# d232_board.net
KiCad netlist of a schematic drawn in EAGLE
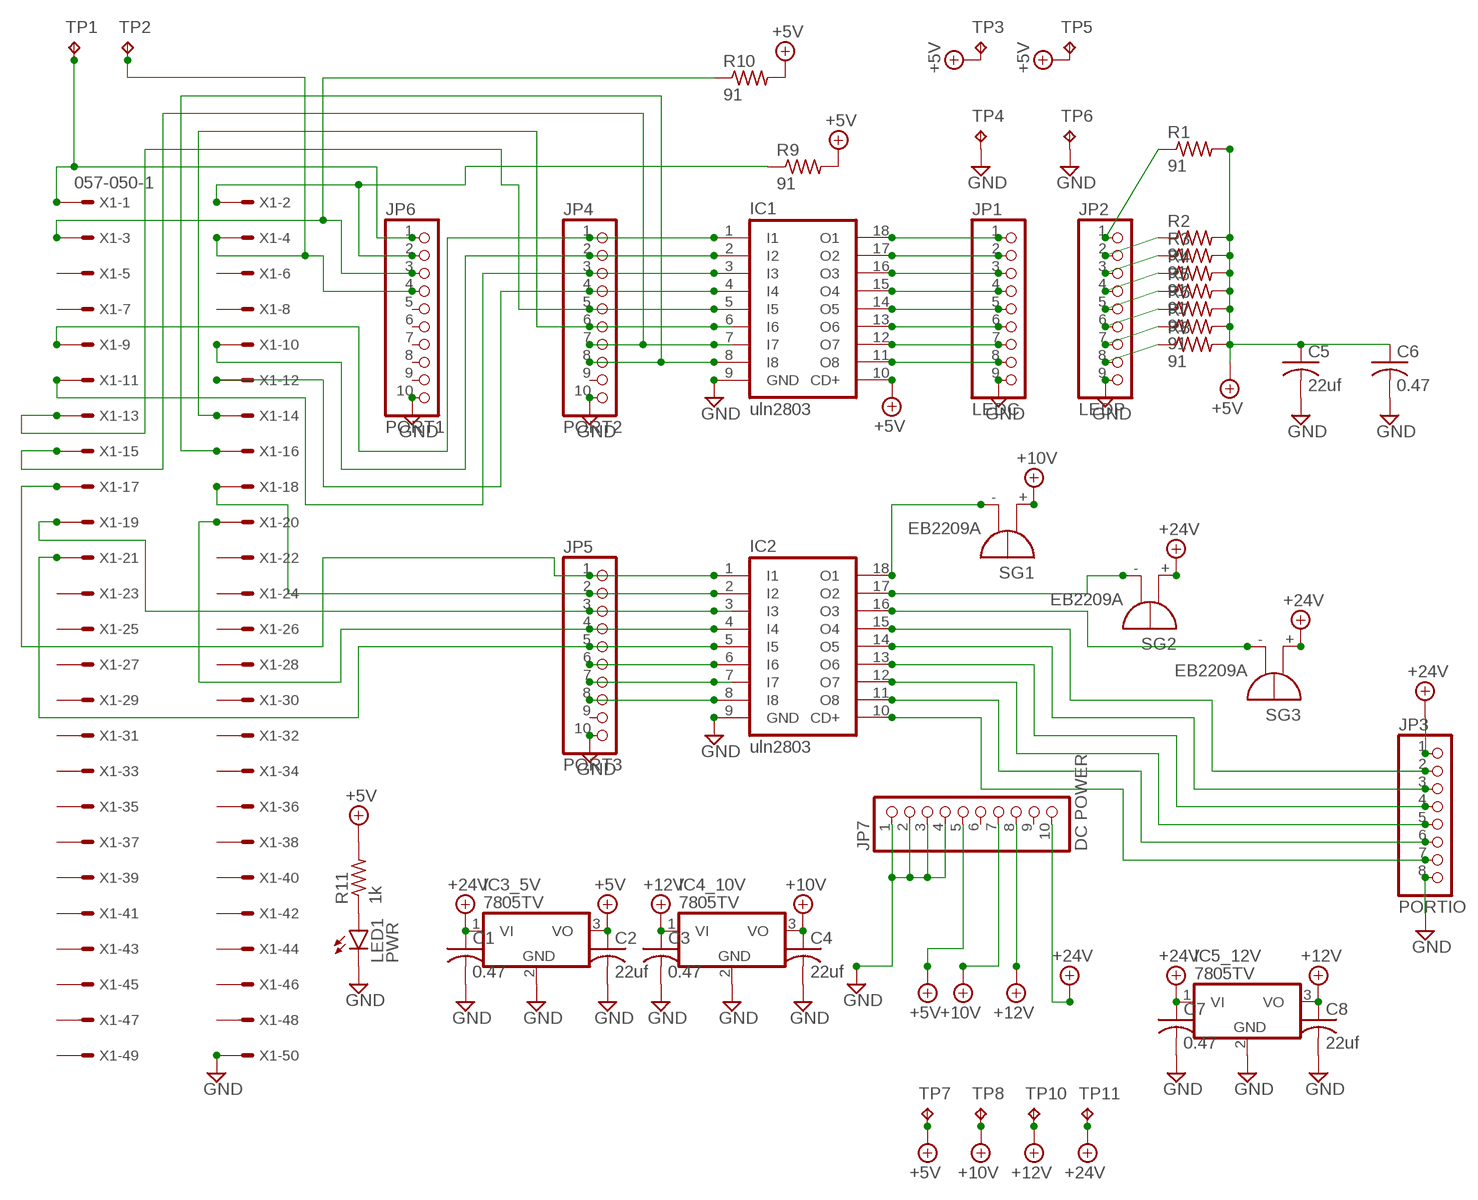
[diagram p0: schematic, sheet 1]

(export (version "E")
  (design (tool "Eeschema 10.0.6"))
  (components
    (comp (ref "C1")
      (value "0.47")
      (footprint "eagle-import:C1206K")
      (libsource (lib "eagle-import") (part "C-USC1206K"))
    )
    (comp (ref "C2")
      (value "22uf")
      (footprint "eagle-import:C1206K")
      (libsource (lib "eagle-import") (part "C-USC1206K"))
    )
    (comp (ref "C3")
      (value "0.47")
      (footprint "eagle-import:C1206K")
      (libsource (lib "eagle-import") (part "C-USC1206K"))
    )
    (comp (ref "C4")
      (value "22uf")
      (footprint "eagle-import:C1206K")
      (libsource (lib "eagle-import") (part "C-USC1206K"))
    )
    (comp (ref "C5")
      (value "22uf")
      (footprint "eagle-import:C1206K")
      (libsource (lib "eagle-import") (part "C-USC1206K"))
    )
    (comp (ref "C6")
      (value "0.47")
      (footprint "eagle-import:C1206K")
      (libsource (lib "eagle-import") (part "C-USC1206K"))
    )
    (comp (ref "C7")
      (value "0.47")
      (footprint "eagle-import:C1206K")
      (libsource (lib "eagle-import") (part "C-USC1206K"))
    )
    (comp (ref "C8")
      (value "22uf")
      (footprint "eagle-import:C1206K")
      (libsource (lib "eagle-import") (part "C-USC1206K"))
    )
    (comp (ref "IC1")
      (value "uln2803")
      (footprint "eagle-import:DIL18")
      (libsource (lib "eagle-import") (part "ULN2803A"))
    )
    (comp (ref "IC2")
      (value "uln2803")
      (footprint "eagle-import:DIL18")
      (libsource (lib "eagle-import") (part "ULN2803A"))
    )
    (comp (ref "IC3_5V")
      (value "7805TV")
      (footprint "eagle-import:TO220V")
      (libsource (lib "eagle-import") (part "78TV05"))
    )
    (comp (ref "IC4_10V")
      (value "7805TV")
      (footprint "eagle-import:TO220V")
      (libsource (lib "eagle-import") (part "78TV05"))
    )
    (comp (ref "IC5_12V")
      (value "7805TV")
      (footprint "eagle-import:TO220V")
      (libsource (lib "eagle-import") (part "78TV05"))
    )
    (comp (ref "JP1")
      (value "LEDC")
      (footprint "eagle-import:1X09")
      (libsource (lib "eagle-import") (part "PINHD-1X9"))
    )
    (comp (ref "JP2")
      (value "LEDP")
      (footprint "eagle-import:1X09")
      (libsource (lib "eagle-import") (part "PINHD-1X9"))
    )
    (comp (ref "JP3")
      (value "PORTIO")
      (footprint "eagle-import:1X08")
      (libsource (lib "eagle-import") (part "PINHD-1X8"))
    )
    (comp (ref "JP4")
      (value "PORT2")
      (footprint "eagle-import:1X10")
      (libsource (lib "eagle-import") (part "PINHD-1X10"))
    )
    (comp (ref "JP5")
      (value "PORT3")
      (footprint "eagle-import:1X10")
      (libsource (lib "eagle-import") (part "PINHD-1X10"))
    )
    (comp (ref "JP6")
      (value "PORT1")
      (footprint "eagle-import:1X10")
      (libsource (lib "eagle-import") (part "PINHD-1X10"))
    )
    (comp (ref "JP7")
      (value "DC POWER")
      (footprint "eagle-import:1X10")
      (libsource (lib "eagle-import") (part "PINHD-1X10"))
    )
    (comp (ref "LED1")
      (value "PWR")
      (footprint "eagle-import:CHIPLED_1206")
      (libsource (lib "eagle-import") (part "LEDCHIPLED_1206"))
    )
    (comp (ref "R1")
      (value "91")
      (footprint "eagle-import:0204V")
      (libsource (lib "eagle-import") (part "R-US_0204/2V"))
    )
    (comp (ref "R2")
      (value "91")
      (footprint "eagle-import:0204V")
      (libsource (lib "eagle-import") (part "R-US_0204/2V"))
    )
    (comp (ref "R3")
      (value "91")
      (footprint "eagle-import:0204V")
      (libsource (lib "eagle-import") (part "R-US_0204/2V"))
    )
    (comp (ref "R4")
      (value "91")
      (footprint "eagle-import:0204V")
      (libsource (lib "eagle-import") (part "R-US_0204/2V"))
    )
    (comp (ref "R5")
      (value "91")
      (footprint "eagle-import:0204V")
      (libsource (lib "eagle-import") (part "R-US_0204/2V"))
    )
    (comp (ref "R6")
      (value "91")
      (footprint "eagle-import:0204V")
      (libsource (lib "eagle-import") (part "R-US_0204/2V"))
    )
    (comp (ref "R7")
      (value "91")
      (footprint "eagle-import:0204V")
      (libsource (lib "eagle-import") (part "R-US_0204/2V"))
    )
    (comp (ref "R8")
      (value "91")
      (footprint "eagle-import:0204V")
      (libsource (lib "eagle-import") (part "R-US_0204/2V"))
    )
    (comp (ref "R9")
      (value "91")
      (footprint "eagle-import:0204V")
      (libsource (lib "eagle-import") (part "R-US_0204/2V"))
    )
    (comp (ref "R10")
      (value "91")
      (footprint "eagle-import:0204V")
      (libsource (lib "eagle-import") (part "R-US_0204/2V"))
    )
    (comp (ref "R11")
      (value "1k")
      (footprint "eagle-import:0204V")
      (libsource (lib "eagle-import") (part "R-US_0204/2V"))
    )
    (comp (ref "SG1")
      (value "EB2209A")
      (footprint "eagle-import:EB2209A")
      (libsource (lib "eagle-import") (part "EB2209A"))
    )
    (comp (ref "SG2")
      (value "EB2209A")
      (footprint "eagle-import:EB2209A")
      (libsource (lib "eagle-import") (part "EB2209A"))
    )
    (comp (ref "SG3")
      (value "EB2209A")
      (footprint "eagle-import:EB2209A")
      (libsource (lib "eagle-import") (part "EB2209A"))
    )
    (comp (ref "TP1")
      (value "TPB2,54")
      (footprint "eagle-import:B2,54")
      (libsource (lib "eagle-import") (part "TPB2,54"))
    )
    (comp (ref "TP2")
      (value "TPB2,54")
      (footprint "eagle-import:B2,54")
      (libsource (lib "eagle-import") (part "TPB2,54"))
    )
    (comp (ref "TP3")
      (value "TPB2,54")
      (footprint "eagle-import:B2,54")
      (libsource (lib "eagle-import") (part "TPB2,54"))
    )
    (comp (ref "TP4")
      (value "TPB2,54")
      (footprint "eagle-import:B2,54")
      (libsource (lib "eagle-import") (part "TPB2,54"))
    )
    (comp (ref "TP5")
      (value "TPB2,54")
      (footprint "eagle-import:B2,54")
      (libsource (lib "eagle-import") (part "TPB2,54"))
    )
    (comp (ref "TP6")
      (value "TPB2,54")
      (footprint "eagle-import:B2,54")
      (libsource (lib "eagle-import") (part "TPB2,54"))
    )
    (comp (ref "TP7")
      (value "TPB2,54")
      (footprint "eagle-import:B2,54")
      (libsource (lib "eagle-import") (part "TPB2,54"))
    )
    (comp (ref "TP8")
      (value "TPB2,54")
      (footprint "eagle-import:B2,54")
      (libsource (lib "eagle-import") (part "TPB2,54"))
    )
    (comp (ref "TP10")
      (value "TPB2,54")
      (footprint "eagle-import:B2,54")
      (libsource (lib "eagle-import") (part "TPB2,54"))
    )
    (comp (ref "TP11")
      (value "TPB2,54")
      (footprint "eagle-import:B2,54")
      (libsource (lib "eagle-import") (part "TPB2,54"))
    )
    (comp (ref "X1")
      (value "057-050-1")
      (footprint "eagle-import:057-050-1")
      (libsource (lib "eagle-import") (part "057-050-1"))
    )
  )
  (nets
    (net (code "1") (name "+5V") (class "Default")
      (node (ref "C2") (pin "1") (pinfunction "1_1") (pintype "passive"))
      (node (ref "C5") (pin "1") (pinfunction "1_1") (pintype "passive"))
      (node (ref "C6") (pin "1") (pinfunction "1_1") (pintype "passive"))
      (node (ref "IC1") (pin "10") (pinfunction "CD+_10") (pintype "passive"))
      (node (ref "IC3_5V") (pin "3") (pinfunction "VO_3") (pintype "passive"))
      (node (ref "JP7") (pin "5") (pinfunction "5_5") (pintype "passive"))
      (node (ref "R1") (pin "2") (pinfunction "2_2") (pintype "passive"))
      (node (ref "R10") (pin "2") (pinfunction "2_2") (pintype "passive"))
      (node (ref "R11") (pin "2") (pinfunction "2_2") (pintype "passive"))
      (node (ref "R2") (pin "2") (pinfunction "2_2") (pintype "passive"))
      (node (ref "R3") (pin "2") (pinfunction "2_2") (pintype "passive"))
      (node (ref "R4") (pin "2") (pinfunction "2_2") (pintype "passive"))
      (node (ref "R5") (pin "2") (pinfunction "2_2") (pintype "passive"))
      (node (ref "R6") (pin "2") (pinfunction "2_2") (pintype "passive"))
      (node (ref "R7") (pin "2") (pinfunction "2_2") (pintype "passive"))
      (node (ref "R8") (pin "2") (pinfunction "2_2") (pintype "passive"))
      (node (ref "R9") (pin "2") (pinfunction "2_2") (pintype "passive"))
      (node (ref "TP3") (pin "TP") (pinfunction "TP_TP") (pintype "input"))
      (node (ref "TP5") (pin "TP") (pinfunction "TP_TP") (pintype "input"))
      (node (ref "TP7") (pin "TP") (pinfunction "TP_TP") (pintype "input"))
    )
    (net (code "2") (name "+10V") (class "Default")
      (node (ref "C4") (pin "1") (pinfunction "1_1") (pintype "passive"))
      (node (ref "IC4_10V") (pin "3") (pinfunction "VO_3") (pintype "passive"))
      (node (ref "JP7") (pin "7") (pinfunction "7_7") (pintype "passive"))
      (node (ref "SG1") (pin "+") (pinfunction "+_+") (pintype "passive"))
      (node (ref "TP8") (pin "TP") (pinfunction "TP_TP") (pintype "input"))
    )
    (net (code "3") (name "+12V") (class "Default")
      (node (ref "C3") (pin "1") (pinfunction "1_1") (pintype "passive"))
      (node (ref "C8") (pin "1") (pinfunction "1_1") (pintype "passive"))
      (node (ref "IC4_10V") (pin "1") (pinfunction "VI_1") (pintype "input"))
      (node (ref "IC5_12V") (pin "3") (pinfunction "VO_3") (pintype "passive"))
      (node (ref "JP7") (pin "8") (pinfunction "8_8") (pintype "passive"))
      (node (ref "TP10") (pin "TP") (pinfunction "TP_TP") (pintype "input"))
    )
    (net (code "4") (name "+24V") (class "Default")
      (node (ref "C1") (pin "1") (pinfunction "1_1") (pintype "passive"))
      (node (ref "C7") (pin "1") (pinfunction "1_1") (pintype "passive"))
      (node (ref "IC3_5V") (pin "1") (pinfunction "VI_1") (pintype "input"))
      (node (ref "IC5_12V") (pin "1") (pinfunction "VI_1") (pintype "input"))
      (node (ref "JP3") (pin "1") (pinfunction "1_1") (pintype "passive"))
      (node (ref "JP7") (pin "10") (pinfunction "10_10") (pintype "passive"))
      (node (ref "SG2") (pin "+") (pinfunction "+_+") (pintype "passive"))
      (node (ref "SG3") (pin "+") (pinfunction "+_+") (pintype "passive"))
      (node (ref "TP11") (pin "TP") (pinfunction "TP_TP") (pintype "input"))
    )
    (net (code "5") (name "GND") (class "Default")
      (node (ref "C1") (pin "2") (pinfunction "2_2") (pintype "passive"))
      (node (ref "C2") (pin "2") (pinfunction "2_2") (pintype "passive"))
      (node (ref "C3") (pin "2") (pinfunction "2_2") (pintype "passive"))
      (node (ref "C4") (pin "2") (pinfunction "2_2") (pintype "passive"))
      (node (ref "C5") (pin "2") (pinfunction "2_2") (pintype "passive"))
      (node (ref "C6") (pin "2") (pinfunction "2_2") (pintype "passive"))
      (node (ref "C7") (pin "2") (pinfunction "2_2") (pintype "passive"))
      (node (ref "C8") (pin "2") (pinfunction "2_2") (pintype "passive"))
      (node (ref "IC1") (pin "9") (pinfunction "GND_9") (pintype "power_in"))
      (node (ref "IC2") (pin "9") (pinfunction "GND_9") (pintype "power_in"))
      (node (ref "IC3_5V") (pin "2") (pinfunction "GND_2") (pintype "passive"))
      (node (ref "IC4_10V") (pin "2") (pinfunction "GND_2") (pintype "passive"))
      (node (ref "IC5_12V") (pin "2") (pinfunction "GND_2") (pintype "passive"))
      (node (ref "JP1") (pin "9") (pinfunction "9_9") (pintype "passive"))
      (node (ref "JP2") (pin "9") (pinfunction "9_9") (pintype "passive"))
      (node (ref "JP3") (pin "8") (pinfunction "8_8") (pintype "passive"))
      (node (ref "JP4") (pin "10") (pinfunction "10_10") (pintype "passive"))
      (node (ref "JP5") (pin "10") (pinfunction "10_10") (pintype "passive"))
      (node (ref "JP6") (pin "10") (pinfunction "10_10") (pintype "passive"))
      (node (ref "JP7") (pin "1") (pinfunction "1_1") (pintype "passive"))
      (node (ref "JP7") (pin "2") (pinfunction "2_2") (pintype "passive"))
      (node (ref "JP7") (pin "3") (pinfunction "3_3") (pintype "passive"))
      (node (ref "JP7") (pin "4") (pinfunction "4_4") (pintype "passive"))
      (node (ref "LED1") (pin "C") (pinfunction "C_C") (pintype "passive"))
      (node (ref "TP4") (pin "TP") (pinfunction "TP_TP") (pintype "input"))
      (node (ref "TP6") (pin "TP") (pinfunction "TP_TP") (pintype "input"))
      (node (ref "X1") (pin "50") (pinfunction "S_50") (pintype "passive"))
    )
    (net (code "6") (name "Net-(IC1-I1)") (class "Default")
      (node (ref "IC1") (pin "1") (pinfunction "I1_1") (pintype "input"))
      (node (ref "JP4") (pin "1") (pinfunction "1_1") (pintype "passive"))
      (node (ref "X1") (pin "9") (pinfunction "S_9") (pintype "passive"))
    )
    (net (code "7") (name "Net-(IC1-I2)") (class "Default")
      (node (ref "IC1") (pin "2") (pinfunction "I2_2") (pintype "input"))
      (node (ref "JP4") (pin "2") (pinfunction "2_2") (pintype "passive"))
      (node (ref "X1") (pin "10") (pinfunction "S_10") (pintype "passive"))
    )
    (net (code "8") (name "Net-(IC1-I3)") (class "Default")
      (node (ref "IC1") (pin "3") (pinfunction "I3_3") (pintype "input"))
      (node (ref "JP4") (pin "3") (pinfunction "3_3") (pintype "passive"))
      (node (ref "X1") (pin "11") (pinfunction "S_11") (pintype "passive"))
    )
    (net (code "9") (name "Net-(IC1-I4)") (class "Default")
      (node (ref "IC1") (pin "4") (pinfunction "I4_4") (pintype "input"))
      (node (ref "JP4") (pin "4") (pinfunction "4_4") (pintype "passive"))
      (node (ref "X1") (pin "12") (pinfunction "S_12") (pintype "passive"))
    )
    (net (code "10") (name "Net-(IC1-I5)") (class "Default")
      (node (ref "IC1") (pin "5") (pinfunction "I5_5") (pintype "input"))
      (node (ref "JP4") (pin "5") (pinfunction "5_5") (pintype "passive"))
      (node (ref "X1") (pin "13") (pinfunction "S_13") (pintype "passive"))
    )
    (net (code "11") (name "Net-(IC1-I6)") (class "Default")
      (node (ref "IC1") (pin "6") (pinfunction "I6_6") (pintype "input"))
      (node (ref "JP4") (pin "6") (pinfunction "6_6") (pintype "passive"))
      (node (ref "X1") (pin "14") (pinfunction "S_14") (pintype "passive"))
    )
    (net (code "12") (name "Net-(IC1-I7)") (class "Default")
      (node (ref "IC1") (pin "7") (pinfunction "I7_7") (pintype "input"))
      (node (ref "JP4") (pin "7") (pinfunction "7_7") (pintype "passive"))
      (node (ref "X1") (pin "15") (pinfunction "S_15") (pintype "passive"))
    )
    (net (code "13") (name "Net-(IC1-I8)") (class "Default")
      (node (ref "IC1") (pin "8") (pinfunction "I8_8") (pintype "input"))
      (node (ref "JP4") (pin "8") (pinfunction "8_8") (pintype "passive"))
      (node (ref "X1") (pin "16") (pinfunction "S_16") (pintype "passive"))
    )
    (net (code "14") (name "Net-(IC1-O1)") (class "Default")
      (node (ref "IC1") (pin "18") (pinfunction "O1_18") (pintype "open_collector"))
      (node (ref "JP1") (pin "1") (pinfunction "1_1") (pintype "passive"))
    )
    (net (code "15") (name "Net-(IC1-O2)") (class "Default")
      (node (ref "IC1") (pin "17") (pinfunction "O2_17") (pintype "open_collector"))
      (node (ref "JP1") (pin "2") (pinfunction "2_2") (pintype "passive"))
    )
    (net (code "16") (name "Net-(IC1-O3)") (class "Default")
      (node (ref "IC1") (pin "16") (pinfunction "O3_16") (pintype "open_collector"))
      (node (ref "JP1") (pin "3") (pinfunction "3_3") (pintype "passive"))
    )
    (net (code "17") (name "Net-(IC1-O4)") (class "Default")
      (node (ref "IC1") (pin "15") (pinfunction "O4_15") (pintype "open_collector"))
      (node (ref "JP1") (pin "4") (pinfunction "4_4") (pintype "passive"))
    )
    (net (code "18") (name "Net-(IC1-O5)") (class "Default")
      (node (ref "IC1") (pin "14") (pinfunction "O5_14") (pintype "open_collector"))
      (node (ref "JP1") (pin "5") (pinfunction "5_5") (pintype "passive"))
    )
    (net (code "19") (name "Net-(IC1-O6)") (class "Default")
      (node (ref "IC1") (pin "13") (pinfunction "O6_13") (pintype "open_collector"))
      (node (ref "JP1") (pin "6") (pinfunction "6_6") (pintype "passive"))
    )
    (net (code "20") (name "Net-(IC1-O7)") (class "Default")
      (node (ref "IC1") (pin "12") (pinfunction "O7_12") (pintype "open_collector"))
      (node (ref "JP1") (pin "7") (pinfunction "7_7") (pintype "passive"))
    )
    (net (code "21") (name "Net-(IC1-O8)") (class "Default")
      (node (ref "IC1") (pin "11") (pinfunction "O8_11") (pintype "open_collector"))
      (node (ref "JP1") (pin "8") (pinfunction "8_8") (pintype "passive"))
    )
    (net (code "22") (name "Net-(IC2-CD+)") (class "Default")
      (node (ref "IC2") (pin "10") (pinfunction "CD+_10") (pintype "passive"))
      (node (ref "JP3") (pin "7") (pinfunction "7_7") (pintype "passive"))
    )
    (net (code "23") (name "Net-(IC2-I1)") (class "Default")
      (node (ref "IC2") (pin "1") (pinfunction "I1_1") (pintype "input"))
      (node (ref "JP5") (pin "1") (pinfunction "1_1") (pintype "passive"))
      (node (ref "X1") (pin "17") (pinfunction "S_17") (pintype "passive"))
    )
    (net (code "24") (name "Net-(IC2-I2)") (class "Default")
      (node (ref "IC2") (pin "2") (pinfunction "I2_2") (pintype "input"))
      (node (ref "JP5") (pin "2") (pinfunction "2_2") (pintype "passive"))
      (node (ref "X1") (pin "18") (pinfunction "S_18") (pintype "passive"))
    )
    (net (code "25") (name "Net-(IC2-I3)") (class "Default")
      (node (ref "IC2") (pin "3") (pinfunction "I3_3") (pintype "input"))
      (node (ref "JP5") (pin "3") (pinfunction "3_3") (pintype "passive"))
      (node (ref "X1") (pin "19") (pinfunction "S_19") (pintype "passive"))
    )
    (net (code "26") (name "Net-(IC2-I4)") (class "Default")
      (node (ref "IC2") (pin "4") (pinfunction "I4_4") (pintype "input"))
      (node (ref "JP5") (pin "4") (pinfunction "4_4") (pintype "passive"))
      (node (ref "X1") (pin "20") (pinfunction "S_20") (pintype "passive"))
    )
    (net (code "27") (name "Net-(IC2-I5)") (class "Default")
      (node (ref "IC2") (pin "5") (pinfunction "I5_5") (pintype "input"))
      (node (ref "JP5") (pin "5") (pinfunction "5_5") (pintype "passive"))
      (node (ref "X1") (pin "21") (pinfunction "S_21") (pintype "passive"))
    )
    (net (code "28") (name "Net-(IC2-I6)") (class "Default")
      (node (ref "IC2") (pin "6") (pinfunction "I6_6") (pintype "input"))
      (node (ref "JP5") (pin "6") (pinfunction "6_6") (pintype "passive"))
    )
    (net (code "29") (name "Net-(IC2-I7)") (class "Default")
      (node (ref "IC2") (pin "7") (pinfunction "I7_7") (pintype "input"))
      (node (ref "JP5") (pin "7") (pinfunction "7_7") (pintype "passive"))
    )
    (net (code "30") (name "Net-(IC2-I8)") (class "Default")
      (node (ref "IC2") (pin "8") (pinfunction "I8_8") (pintype "input"))
      (node (ref "JP5") (pin "8") (pinfunction "8_8") (pintype "passive"))
    )
    (net (code "31") (name "Net-(IC2-O1)") (class "Default")
      (node (ref "IC2") (pin "18") (pinfunction "O1_18") (pintype "open_collector"))
      (node (ref "SG1") (pin "-") (pinfunction "-_-") (pintype "passive"))
    )
    (net (code "32") (name "Net-(IC2-O2)") (class "Default")
      (node (ref "IC2") (pin "17") (pinfunction "O2_17") (pintype "open_collector"))
      (node (ref "SG2") (pin "-") (pinfunction "-_-") (pintype "passive"))
    )
    (net (code "33") (name "Net-(IC2-O3)") (class "Default")
      (node (ref "IC2") (pin "16") (pinfunction "O3_16") (pintype "open_collector"))
      (node (ref "SG3") (pin "-") (pinfunction "-_-") (pintype "passive"))
    )
    (net (code "34") (name "Net-(IC2-O4)") (class "Default")
      (node (ref "IC2") (pin "15") (pinfunction "O4_15") (pintype "open_collector"))
      (node (ref "JP3") (pin "2") (pinfunction "2_2") (pintype "passive"))
    )
    (net (code "35") (name "Net-(IC2-O5)") (class "Default")
      (node (ref "IC2") (pin "14") (pinfunction "O5_14") (pintype "open_collector"))
      (node (ref "JP3") (pin "3") (pinfunction "3_3") (pintype "passive"))
    )
    (net (code "36") (name "Net-(IC2-O6)") (class "Default")
      (node (ref "IC2") (pin "13") (pinfunction "O6_13") (pintype "open_collector"))
      (node (ref "JP3") (pin "4") (pinfunction "4_4") (pintype "passive"))
    )
    (net (code "37") (name "Net-(IC2-O7)") (class "Default")
      (node (ref "IC2") (pin "12") (pinfunction "O7_12") (pintype "open_collector"))
      (node (ref "JP3") (pin "5") (pinfunction "5_5") (pintype "passive"))
    )
    (net (code "38") (name "Net-(IC2-O8)") (class "Default")
      (node (ref "IC2") (pin "11") (pinfunction "O8_11") (pintype "open_collector"))
      (node (ref "JP3") (pin "6") (pinfunction "6_6") (pintype "passive"))
    )
    (net (code "39") (name "Net-(JP2-Pad1)") (class "Default")
      (node (ref "JP2") (pin "1") (pinfunction "1_1") (pintype "passive"))
      (node (ref "R1") (pin "1") (pinfunction "1_1") (pintype "passive"))
    )
    (net (code "40") (name "Net-(JP2-Pad2)") (class "Default")
      (node (ref "JP2") (pin "2") (pinfunction "2_2") (pintype "passive"))
      (node (ref "R2") (pin "1") (pinfunction "1_1") (pintype "passive"))
    )
    (net (code "41") (name "Net-(JP2-Pad3)") (class "Default")
      (node (ref "JP2") (pin "3") (pinfunction "3_3") (pintype "passive"))
      (node (ref "R3") (pin "1") (pinfunction "1_1") (pintype "passive"))
    )
    (net (code "42") (name "Net-(JP2-Pad4)") (class "Default")
      (node (ref "JP2") (pin "4") (pinfunction "4_4") (pintype "passive"))
      (node (ref "R4") (pin "1") (pinfunction "1_1") (pintype "passive"))
    )
    (net (code "43") (name "Net-(JP2-Pad5)") (class "Default")
      (node (ref "JP2") (pin "5") (pinfunction "5_5") (pintype "passive"))
      (node (ref "R5") (pin "1") (pinfunction "1_1") (pintype "passive"))
    )
    (net (code "44") (name "Net-(JP2-Pad6)") (class "Default")
      (node (ref "JP2") (pin "6") (pinfunction "6_6") (pintype "passive"))
      (node (ref "R6") (pin "1") (pinfunction "1_1") (pintype "passive"))
    )
    (net (code "45") (name "Net-(JP2-Pad7)") (class "Default")
      (node (ref "JP2") (pin "7") (pinfunction "7_7") (pintype "passive"))
      (node (ref "R7") (pin "1") (pinfunction "1_1") (pintype "passive"))
    )
    (net (code "46") (name "Net-(JP2-Pad8)") (class "Default")
      (node (ref "JP2") (pin "8") (pinfunction "8_8") (pintype "passive"))
      (node (ref "R8") (pin "1") (pinfunction "1_1") (pintype "passive"))
    )
    (net (code "47") (name "Net-(LED1-PadA)") (class "Default")
      (node (ref "LED1") (pin "A") (pinfunction "A_A") (pintype "passive"))
      (node (ref "R11") (pin "1") (pinfunction "1_1") (pintype "passive"))
    )
    (net (code "48") (name "Net-(X1A-S)") (class "Default")
      (node (ref "JP6") (pin "1") (pinfunction "1_1") (pintype "passive"))
      (node (ref "TP1") (pin "TP") (pinfunction "TP_TP") (pintype "input"))
      (node (ref "X1") (pin "1") (pinfunction "S_1") (pintype "passive"))
    )
    (net (code "49") (name "Net-(X1AH-S)") (class "Default")
      (node (ref "JP6") (pin "4") (pinfunction "4_4") (pintype "passive"))
      (node (ref "TP2") (pin "TP") (pinfunction "TP_TP") (pintype "input"))
      (node (ref "X1") (pin "4") (pinfunction "S_4") (pintype "passive"))
    )
    (net (code "50") (name "Net-(X1L-S)") (class "Default")
      (node (ref "JP6") (pin "2") (pinfunction "2_2") (pintype "passive"))
      (node (ref "R9") (pin "1") (pinfunction "1_1") (pintype "passive"))
      (node (ref "X1") (pin "2") (pinfunction "S_2") (pintype "passive"))
    )
    (net (code "51") (name "Net-(X1W-S)") (class "Default")
      (node (ref "JP6") (pin "3") (pinfunction "3_3") (pintype "passive"))
      (node (ref "R10") (pin "1") (pinfunction "1_1") (pintype "passive"))
      (node (ref "X1") (pin "3") (pinfunction "S_3") (pintype "passive"))
    )
    (net (code "52") (name "unconnected-(JP4-Pad9)") (class "Default")
      (node (ref "JP4") (pin "9") (pinfunction "9_9") (pintype "passive"))
    )
    (net (code "53") (name "unconnected-(JP5-Pad9)") (class "Default")
      (node (ref "JP5") (pin "9") (pinfunction "9_9") (pintype "passive"))
    )
    (net (code "54") (name "unconnected-(JP6-Pad5)") (class "Default")
      (node (ref "JP6") (pin "5") (pinfunction "5_5") (pintype "passive"))
    )
    (net (code "55") (name "unconnected-(JP6-Pad6)") (class "Default")
      (node (ref "JP6") (pin "6") (pinfunction "6_6") (pintype "passive"))
    )
    (net (code "56") (name "unconnected-(JP6-Pad7)") (class "Default")
      (node (ref "JP6") (pin "7") (pinfunction "7_7") (pintype "passive"))
    )
    (net (code "57") (name "unconnected-(JP6-Pad8)") (class "Default")
      (node (ref "JP6") (pin "8") (pinfunction "8_8") (pintype "passive"))
    )
    (net (code "58") (name "unconnected-(JP6-Pad9)") (class "Default")
      (node (ref "JP6") (pin "9") (pinfunction "9_9") (pintype "passive"))
    )
    (net (code "59") (name "unconnected-(JP7-Pad6)") (class "Default")
      (node (ref "JP7") (pin "6") (pinfunction "6_6") (pintype "passive"))
    )
    (net (code "60") (name "unconnected-(JP7-Pad9)") (class "Default")
      (node (ref "JP7") (pin "9") (pinfunction "9_9") (pintype "passive"))
    )
    (net (code "61") (name "unconnected-(X1AA-S-Pad33)") (class "Default")
      (node (ref "X1") (pin "33") (pinfunction "S_33") (pintype "passive"))
    )
    (net (code "62") (name "unconnected-(X1AB-S-Pad34)") (class "Default")
      (node (ref "X1") (pin "34") (pinfunction "S_34") (pintype "passive"))
    )
    (net (code "63") (name "unconnected-(X1AC-S-Pad35)") (class "Default")
      (node (ref "X1") (pin "35") (pinfunction "S_35") (pintype "passive"))
    )
    (net (code "64") (name "unconnected-(X1AD-S-Pad36)") (class "Default")
      (node (ref "X1") (pin "36") (pinfunction "S_36") (pintype "passive"))
    )
    (net (code "65") (name "unconnected-(X1AE-S-Pad37)") (class "Default")
      (node (ref "X1") (pin "37") (pinfunction "S_37") (pintype "passive"))
    )
    (net (code "66") (name "unconnected-(X1AF-S-Pad38)") (class "Default")
      (node (ref "X1") (pin "38") (pinfunction "S_38") (pintype "passive"))
    )
    (net (code "67") (name "unconnected-(X1AG-S-Pad39)") (class "Default")
      (node (ref "X1") (pin "39") (pinfunction "S_39") (pintype "passive"))
    )
    (net (code "68") (name "unconnected-(X1AI-S-Pad40)") (class "Default")
      (node (ref "X1") (pin "40") (pinfunction "S_40") (pintype "passive"))
    )
    (net (code "69") (name "unconnected-(X1AJ-S-Pad41)") (class "Default")
      (node (ref "X1") (pin "41") (pinfunction "S_41") (pintype "passive"))
    )
    (net (code "70") (name "unconnected-(X1AK-S-Pad42)") (class "Default")
      (node (ref "X1") (pin "42") (pinfunction "S_42") (pintype "passive"))
    )
    (net (code "71") (name "unconnected-(X1AL-S-Pad43)") (class "Default")
      (node (ref "X1") (pin "43") (pinfunction "S_43") (pintype "passive"))
    )
    (net (code "72") (name "unconnected-(X1AM-S-Pad44)") (class "Default")
      (node (ref "X1") (pin "44") (pinfunction "S_44") (pintype "passive"))
    )
    (net (code "73") (name "unconnected-(X1AN-S-Pad45)") (class "Default")
      (node (ref "X1") (pin "45") (pinfunction "S_45") (pintype "passive"))
    )
    (net (code "74") (name "unconnected-(X1AO-S-Pad46)") (class "Default")
      (node (ref "X1") (pin "46") (pinfunction "S_46") (pintype "passive"))
    )
    (net (code "75") (name "unconnected-(X1AP-S-Pad47)") (class "Default")
      (node (ref "X1") (pin "47") (pinfunction "S_47") (pintype "passive"))
    )
    (net (code "76") (name "unconnected-(X1AQ-S-Pad48)") (class "Default")
      (node (ref "X1") (pin "48") (pinfunction "S_48") (pintype "passive"))
    )
    (net (code "77") (name "unconnected-(X1AR-S-Pad49)") (class "Default")
      (node (ref "X1") (pin "49") (pinfunction "S_49") (pintype "passive"))
    )
    (net (code "78") (name "unconnected-(X1AS-S-Pad5)") (class "Default")
      (node (ref "X1") (pin "5") (pinfunction "S_5") (pintype "passive"))
    )
    (net (code "79") (name "unconnected-(X1AU-S-Pad6)") (class "Default")
      (node (ref "X1") (pin "6") (pinfunction "S_6") (pintype "passive"))
    )
    (net (code "80") (name "unconnected-(X1AV-S-Pad7)") (class "Default")
      (node (ref "X1") (pin "7") (pinfunction "S_7") (pintype "passive"))
    )
    (net (code "81") (name "unconnected-(X1AW-S-Pad8)") (class "Default")
      (node (ref "X1") (pin "8") (pinfunction "S_8") (pintype "passive"))
    )
    (net (code "82") (name "unconnected-(X1O-S-Pad22)") (class "Default")
      (node (ref "X1") (pin "22") (pinfunction "S_22") (pintype "passive"))
    )
    (net (code "83") (name "unconnected-(X1P-S-Pad23)") (class "Default")
      (node (ref "X1") (pin "23") (pinfunction "S_23") (pintype "passive"))
    )
    (net (code "84") (name "unconnected-(X1Q-S-Pad24)") (class "Default")
      (node (ref "X1") (pin "24") (pinfunction "S_24") (pintype "passive"))
    )
    (net (code "85") (name "unconnected-(X1R-S-Pad25)") (class "Default")
      (node (ref "X1") (pin "25") (pinfunction "S_25") (pintype "passive"))
    )
    (net (code "86") (name "unconnected-(X1S-S-Pad26)") (class "Default")
      (node (ref "X1") (pin "26") (pinfunction "S_26") (pintype "passive"))
    )
    (net (code "87") (name "unconnected-(X1T-S-Pad27)") (class "Default")
      (node (ref "X1") (pin "27") (pinfunction "S_27") (pintype "passive"))
    )
    (net (code "88") (name "unconnected-(X1U-S-Pad28)") (class "Default")
      (node (ref "X1") (pin "28") (pinfunction "S_28") (pintype "passive"))
    )
    (net (code "89") (name "unconnected-(X1V-S-Pad29)") (class "Default")
      (node (ref "X1") (pin "29") (pinfunction "S_29") (pintype "passive"))
    )
    (net (code "90") (name "unconnected-(X1X-S-Pad30)") (class "Default")
      (node (ref "X1") (pin "30") (pinfunction "S_30") (pintype "passive"))
    )
    (net (code "91") (name "unconnected-(X1Y-S-Pad31)") (class "Default")
      (node (ref "X1") (pin "31") (pinfunction "S_31") (pintype "passive"))
    )
    (net (code "92") (name "unconnected-(X1Z-S-Pad32)") (class "Default")
      (node (ref "X1") (pin "32") (pinfunction "S_32") (pintype "passive"))
    )
  )
)
